# Led7_74HC595.net
KiCad netlist of a schematic drawn in Altium Designer
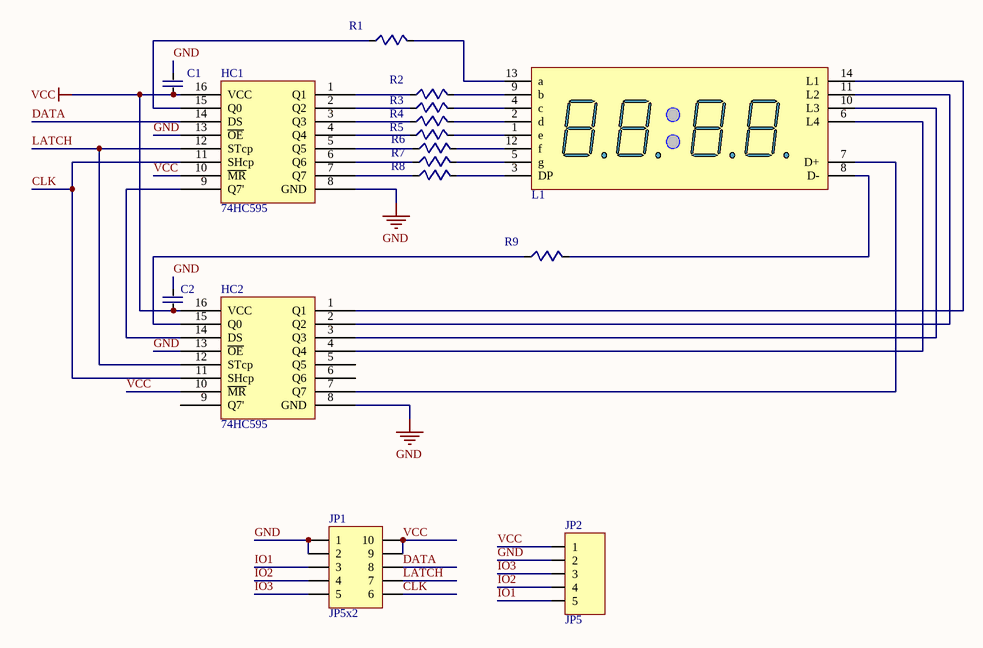
[diagram p0: Led7_74HC595.SchDoc]

(export (version "E")
  (design (tool "Eeschema 10.0.6"))
  (components
    (comp (ref "C1")
      (value "100n Cer")
      (footprint "CAPC_0805")
      (description "CAP CER 0.1UF 25V 10% X7R 0805")
      (libsource (lib "EngineersLife") (part "CAPC0805_104"))
    )
    (comp (ref "C2")
      (value "100n Cer")
      (footprint "CAPC_0805")
      (description "CAP CER 0.1UF 25V 10% X7R 0805")
      (libsource (lib "EngineersLife") (part "CAPC0805_104"))
    )
    (comp (ref "HC1")
      (value "74HC595")
      (footprint "SOIC_16")
      (libsource (lib "EngineersLife") (part "74HC595"))
    )
    (comp (ref "HC2")
      (value "74HC595")
      (footprint "SOIC_16")
      (libsource (lib "EngineersLife") (part "74HC595"))
    )
    (comp (ref "JP1")
      (value "JP5x2")
      (footprint "JP5-D2T")
      (description "WR-PHD 2.54 mm Dual Socket Header")
      (fields
        (field (name "MANUFACTURER") "Würth Elektronik eiSos GmbH")
        (field (name "PARTNO") "61301021821")
        (field (name "CREATED BY") "Karrer Zheng")
      )
      (libsource (lib "EngineersLife") (part "JP5x2"))
    )
    (comp (ref "JP2")
      (value "JP5")
      (footprint "JP5-C1T")
      (description "WR-PHD 2.54 mm Angled Socket Header")
      (fields
        (field (name "MANUFACTURER") "Würth Elektronik eiSos GmbH")
        (field (name "PARTNO") "613005143121")
        (field (name "CREATED BY") "Karrer Zheng")
      )
      (libsource (lib "EngineersLife") (part "JP5"))
    )
    (comp (ref "L1")
      (value "Led 7 Seg 4 digit - Anode")
      (footprint "LED7SEG-4-0.56-RG")
      (libsource (lib "EngineersLife") (part "LED7SEG-4-RG"))
    )
    (comp (ref "R1")
      (value "RC0805FR-07100RL")
      (footprint "RESC_0805")
      (description "RES SMD 100 OHM 1% 1/8W 0805")
      (libsource (lib "EngineersLife") (part "RES0805_100R"))
    )
    (comp (ref "R2")
      (value "RC0805FR-07100RL")
      (footprint "RESC_0805")
      (description "RES SMD 100 OHM 1% 1/8W 0805")
      (libsource (lib "EngineersLife") (part "RES0805_100R"))
    )
    (comp (ref "R3")
      (value "RC0805FR-07100RL")
      (footprint "RESC_0805")
      (description "RES SMD 100 OHM 1% 1/8W 0805")
      (libsource (lib "EngineersLife") (part "RES0805_100R"))
    )
    (comp (ref "R4")
      (value "RC0805FR-07100RL")
      (footprint "RESC_0805")
      (description "RES SMD 100 OHM 1% 1/8W 0805")
      (libsource (lib "EngineersLife") (part "RES0805_100R"))
    )
    (comp (ref "R5")
      (value "RC0805FR-07100RL")
      (footprint "RESC_0805")
      (description "RES SMD 100 OHM 1% 1/8W 0805")
      (libsource (lib "EngineersLife") (part "RES0805_100R"))
    )
    (comp (ref "R6")
      (value "RC0805FR-07100RL")
      (footprint "RESC_0805")
      (description "RES SMD 100 OHM 1% 1/8W 0805")
      (libsource (lib "EngineersLife") (part "RES0805_100R"))
    )
    (comp (ref "R7")
      (value "RC0805FR-07100RL")
      (footprint "RESC_0805")
      (description "RES SMD 100 OHM 1% 1/8W 0805")
      (libsource (lib "EngineersLife") (part "RES0805_100R"))
    )
    (comp (ref "R8")
      (value "RC0805FR-07100RL")
      (footprint "RESC_0805")
      (description "RES SMD 100 OHM 1% 1/8W 0805")
      (libsource (lib "EngineersLife") (part "RES0805_100R"))
    )
    (comp (ref "R9")
      (value "RC0805FR-07100RL")
      (footprint "RESC_0805")
      (description "RES SMD 100 OHM 1% 1/8W 0805")
      (libsource (lib "EngineersLife") (part "RES0805_100R"))
    )
  )
  (nets
    (net (code "1") (name "/CLK") (class "Default")
      (node (ref "HC1") (pin "11") (pinfunction "SHcp_11") (pintype "passive"))
      (node (ref "HC2") (pin "11") (pinfunction "SHcp_11") (pintype "passive"))
      (node (ref "JP1") (pin "6") (pinfunction "6_6") (pintype "passive"))
    )
    (net (code "2") (name "/DATA") (class "Default")
      (node (ref "HC1") (pin "14") (pinfunction "DS_14") (pintype "passive"))
      (node (ref "JP1") (pin "8") (pinfunction "8_8") (pintype "passive"))
    )
    (net (code "3") (name "/IO1") (class "Default")
      (node (ref "JP1") (pin "3") (pinfunction "3_3") (pintype "passive"))
      (node (ref "JP2") (pin "5") (pinfunction "5_5") (pintype "passive"))
    )
    (net (code "4") (name "/IO2") (class "Default")
      (node (ref "JP1") (pin "4") (pinfunction "4_4") (pintype "passive"))
      (node (ref "JP2") (pin "4") (pinfunction "4_4") (pintype "passive"))
    )
    (net (code "5") (name "/IO3") (class "Default")
      (node (ref "JP1") (pin "5") (pinfunction "5_5") (pintype "passive"))
      (node (ref "JP2") (pin "3") (pinfunction "3_3") (pintype "passive"))
    )
    (net (code "6") (name "/LATCH") (class "Default")
      (node (ref "HC1") (pin "12") (pinfunction "STcp_12") (pintype "passive"))
      (node (ref "HC2") (pin "12") (pinfunction "STcp_12") (pintype "passive"))
      (node (ref "JP1") (pin "7") (pinfunction "7_7") (pintype "passive"))
    )
    (net (code "7") (name "GND") (class "Default")
      (node (ref "C1") (pin "2") (pinfunction "2_2") (pintype "passive"))
      (node (ref "C2") (pin "2") (pinfunction "2_2") (pintype "passive"))
      (node (ref "HC1") (pin "13") (pinfunction "~{OE}_13") (pintype "passive"))
      (node (ref "HC1") (pin "8") (pinfunction "GND_8") (pintype "passive"))
      (node (ref "HC2") (pin "13") (pinfunction "~{OE}_13") (pintype "passive"))
      (node (ref "HC2") (pin "8") (pinfunction "GND_8") (pintype "passive"))
      (node (ref "JP1") (pin "1") (pinfunction "1_1") (pintype "passive"))
      (node (ref "JP1") (pin "2") (pinfunction "2_2") (pintype "passive"))
      (node (ref "JP2") (pin "2") (pinfunction "2_2") (pintype "passive"))
    )
    (net (code "8") (name "Net-(HC1-Q0)") (class "Default")
      (node (ref "HC1") (pin "15") (pinfunction "Q0_15") (pintype "passive"))
      (node (ref "R1") (pin "1") (pinfunction "1_1") (pintype "passive"))
    )
    (net (code "9") (name "Net-(HC1-Q1)") (class "Default")
      (node (ref "HC1") (pin "1") (pinfunction "Q1_1") (pintype "passive"))
      (node (ref "R2") (pin "1") (pinfunction "1_1") (pintype "passive"))
    )
    (net (code "10") (name "Net-(HC1-Q2)") (class "Default")
      (node (ref "HC1") (pin "2") (pinfunction "Q2_2") (pintype "passive"))
      (node (ref "R3") (pin "1") (pinfunction "1_1") (pintype "passive"))
    )
    (net (code "11") (name "Net-(HC1-Q3)") (class "Default")
      (node (ref "HC1") (pin "3") (pinfunction "Q3_3") (pintype "passive"))
      (node (ref "R4") (pin "1") (pinfunction "1_1") (pintype "passive"))
    )
    (net (code "12") (name "Net-(HC1-Q4)") (class "Default")
      (node (ref "HC1") (pin "4") (pinfunction "Q4_4") (pintype "passive"))
      (node (ref "R5") (pin "1") (pinfunction "1_1") (pintype "passive"))
    )
    (net (code "13") (name "Net-(HC1-Q5)") (class "Default")
      (node (ref "HC1") (pin "5") (pinfunction "Q5_5") (pintype "passive"))
      (node (ref "R6") (pin "1") (pinfunction "1_1") (pintype "passive"))
    )
    (net (code "14") (name "Net-(HC1-Q6)") (class "Default")
      (node (ref "HC1") (pin "6") (pinfunction "Q6_6") (pintype "passive"))
      (node (ref "R7") (pin "1") (pinfunction "1_1") (pintype "passive"))
    )
    (net (code "15") (name "Net-(HC1-Q7')") (class "Default")
      (node (ref "HC1") (pin "9") (pinfunction "Q7'_9") (pintype "passive"))
      (node (ref "HC2") (pin "14") (pinfunction "DS_14") (pintype "passive"))
    )
    (net (code "16") (name "Net-(HC1-Q7)") (class "Default")
      (node (ref "HC1") (pin "7") (pinfunction "Q7_7") (pintype "passive"))
      (node (ref "R8") (pin "1") (pinfunction "1_1") (pintype "passive"))
    )
    (net (code "17") (name "Net-(HC2-Q0)") (class "Default")
      (node (ref "HC2") (pin "15") (pinfunction "Q0_15") (pintype "passive"))
      (node (ref "R9") (pin "1") (pinfunction "1_1") (pintype "passive"))
    )
    (net (code "18") (name "Net-(HC2-Q1)") (class "Default")
      (node (ref "HC2") (pin "1") (pinfunction "Q1_1") (pintype "passive"))
      (node (ref "L1") (pin "14") (pinfunction "L1_14") (pintype "passive"))
    )
    (net (code "19") (name "Net-(HC2-Q2)") (class "Default")
      (node (ref "HC2") (pin "2") (pinfunction "Q2_2") (pintype "passive"))
      (node (ref "L1") (pin "11") (pinfunction "L2_11") (pintype "passive"))
    )
    (net (code "20") (name "Net-(HC2-Q3)") (class "Default")
      (node (ref "HC2") (pin "3") (pinfunction "Q3_3") (pintype "passive"))
      (node (ref "L1") (pin "10") (pinfunction "L3_10") (pintype "passive"))
    )
    (net (code "21") (name "Net-(HC2-Q4)") (class "Default")
      (node (ref "HC2") (pin "4") (pinfunction "Q4_4") (pintype "passive"))
      (node (ref "L1") (pin "6") (pinfunction "L4_6") (pintype "passive"))
    )
    (net (code "22") (name "Net-(HC2-Q7)") (class "Default")
      (node (ref "HC2") (pin "7") (pinfunction "Q7_7") (pintype "passive"))
      (node (ref "L1") (pin "7") (pinfunction "D+_7") (pintype "passive"))
    )
    (net (code "23") (name "Net-(L1-D-)") (class "Default")
      (node (ref "L1") (pin "8") (pinfunction "D-_8") (pintype "passive"))
      (node (ref "R9") (pin "2") (pinfunction "2_2") (pintype "passive"))
    )
    (net (code "24") (name "Net-(L1-DP)") (class "Default")
      (node (ref "L1") (pin "3") (pinfunction "DP_3") (pintype "passive"))
      (node (ref "R8") (pin "2") (pinfunction "2_2") (pintype "passive"))
    )
    (net (code "25") (name "Net-(L1-a)") (class "Default")
      (node (ref "L1") (pin "13") (pinfunction "a_13") (pintype "passive"))
      (node (ref "R1") (pin "2") (pinfunction "2_2") (pintype "passive"))
    )
    (net (code "26") (name "Net-(L1-b)") (class "Default")
      (node (ref "L1") (pin "9") (pinfunction "b_9") (pintype "passive"))
      (node (ref "R2") (pin "2") (pinfunction "2_2") (pintype "passive"))
    )
    (net (code "27") (name "Net-(L1-c)") (class "Default")
      (node (ref "L1") (pin "4") (pinfunction "c_4") (pintype "passive"))
      (node (ref "R3") (pin "2") (pinfunction "2_2") (pintype "passive"))
    )
    (net (code "28") (name "Net-(L1-d)") (class "Default")
      (node (ref "L1") (pin "2") (pinfunction "d_2") (pintype "passive"))
      (node (ref "R4") (pin "2") (pinfunction "2_2") (pintype "passive"))
    )
    (net (code "29") (name "Net-(L1-e)") (class "Default")
      (node (ref "L1") (pin "1") (pinfunction "e_1") (pintype "passive"))
      (node (ref "R5") (pin "2") (pinfunction "2_2") (pintype "passive"))
    )
    (net (code "30") (name "Net-(L1-f)") (class "Default")
      (node (ref "L1") (pin "12") (pinfunction "f_12") (pintype "passive"))
      (node (ref "R6") (pin "2") (pinfunction "2_2") (pintype "passive"))
    )
    (net (code "31") (name "Net-(L1-g)") (class "Default")
      (node (ref "L1") (pin "5") (pinfunction "g_5") (pintype "passive"))
      (node (ref "R7") (pin "2") (pinfunction "2_2") (pintype "passive"))
    )
    (net (code "32") (name "VCC") (class "Default")
      (node (ref "C1") (pin "1") (pinfunction "1_1") (pintype "passive"))
      (node (ref "C2") (pin "1") (pinfunction "1_1") (pintype "passive"))
      (node (ref "HC1") (pin "10") (pinfunction "~{MR}_10") (pintype "passive"))
      (node (ref "HC1") (pin "16") (pinfunction "VCC_16") (pintype "passive"))
      (node (ref "HC2") (pin "10") (pinfunction "~{MR}_10") (pintype "passive"))
      (node (ref "HC2") (pin "16") (pinfunction "VCC_16") (pintype "passive"))
      (node (ref "JP1") (pin "10") (pinfunction "10_10") (pintype "passive"))
      (node (ref "JP1") (pin "9") (pinfunction "9_9") (pintype "passive"))
      (node (ref "JP2") (pin "1") (pinfunction "1_1") (pintype "passive"))
    )
    (net (code "33") (name "unconnected-(HC2-Q5-Pad5)") (class "Default")
      (node (ref "HC2") (pin "5") (pinfunction "Q5_5") (pintype "passive"))
    )
    (net (code "34") (name "unconnected-(HC2-Q6-Pad6)") (class "Default")
      (node (ref "HC2") (pin "6") (pinfunction "Q6_6") (pintype "passive"))
    )
    (net (code "35") (name "unconnected-(HC2-Q7'-Pad9)") (class "Default")
      (node (ref "HC2") (pin "9") (pinfunction "Q7'_9") (pintype "passive"))
    )
  )
)
